# FPGA_IO.net
KiCad netlist of a schematic drawn in Altium Designer
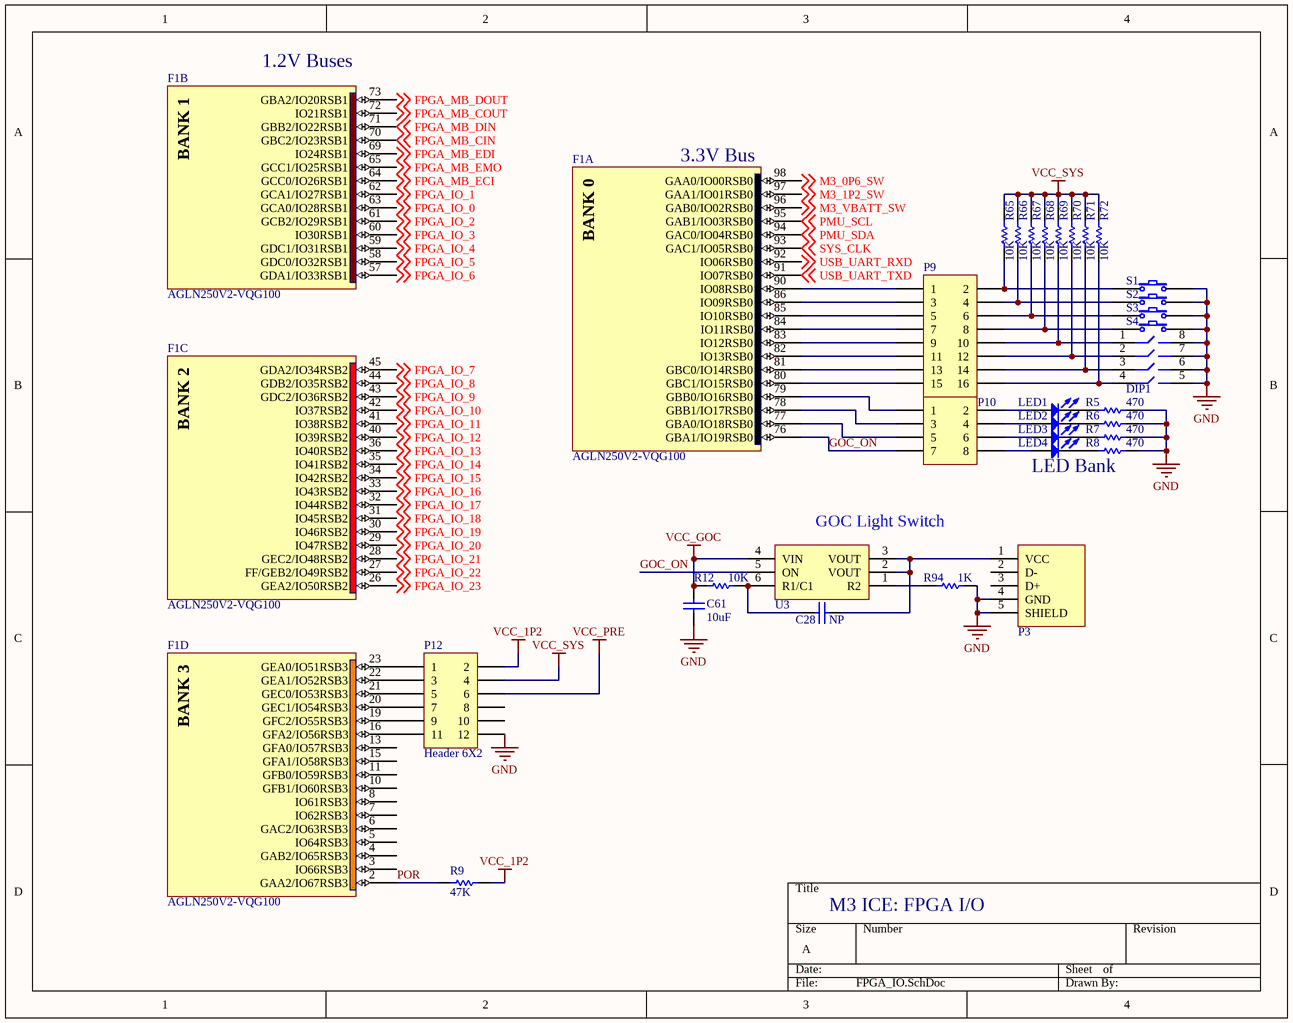
[diagram p0: FPGA_IO.SchDoc]

(export (version "E")
  (design (tool "Eeschema 10.0.6"))
  (components
    (comp (ref "C28")
      (value "NP")
      (footprint "0402")
      (description "Capacitor (Semiconductor SIM Model)")
      (fields (field (name "Comment") "Cap Semi") (field (name "PUBLISHER") "Altium Limited"))
      (libsource (lib "Miscellaneous Devices") (part "Cap Semi"))
    )
    (comp (ref "C61")
      (value "10uF")
      (footprint "0805")
      (description "Capacitor (Semiconductor SIM Model)")
      (fields
        (field (name "DISTPARTNO") "445-6857-1-ND")
        (field (name "MANPARTNO") "C2012X7R1A106K")
        (field (name "PUBLISHER") "Altium Limited")
      )
      (libsource (lib "M3") (part "Cap Chip"))
    )
    (comp (ref "DIP1")
      (value "ADE0404")
      (footprint "DIP-8")
      (description "4-DIP Switch")
      (fields (field (name "DISTPARTNO") "450-1364-ND"))
      (libsource (lib "M3") (part "ADE0404"))
    )
    (comp (ref "F1")
      (value "AGLN250V2-VQG100")
      (footprint "VQ100_N")
      (fields (field (name "DISTPARTNO") "1100-1134-ND") (field (name "PUBLISHER") "Altium Limited"))
      (libsource (lib "Actel IGLOO nano") (part "AGLN250V2-VQG100"))
    )
    (comp (ref "LED1")
      (value "LED 1206")
      (footprint "1206_LED")
      (fields (field (name "DISTPARTNO") "160-1169-1-ND") (field (name "MANPARTNO") "LTST-C150GKT"))
      (libsource (lib "M3") (part "LED 1206"))
    )
    (comp (ref "LED2")
      (value "LED 1206")
      (footprint "1206_LED")
      (fields (field (name "DISTPARTNO") "160-1169-1-ND") (field (name "MANPARTNO") "LTST-C150GKT"))
      (libsource (lib "M3") (part "LED 1206"))
    )
    (comp (ref "LED3")
      (value "LED 1206")
      (footprint "1206_LED")
      (fields (field (name "DISTPARTNO") "160-1169-1-ND") (field (name "MANPARTNO") "LTST-C150GKT"))
      (libsource (lib "M3") (part "LED 1206"))
    )
    (comp (ref "LED4")
      (value "LED 1206")
      (footprint "1206_LED")
      (fields (field (name "DISTPARTNO") "160-1169-1-ND") (field (name "MANPARTNO") "LTST-C150GKT"))
      (libsource (lib "M3") (part "LED 1206"))
    )
    (comp (ref "P3")
      (value "USB_HORIZONTAL")
      (footprint "USB_HORIZONTAL")
      (fields (field (name "DISTPARTNO") "A31726-ND") (field (name "MANPARTNO") "292303-1"))
      (libsource (lib "M3") (part "USB_HORIZONTAL"))
    )
    (comp (ref "P9")
      (value "Header 8X2")
      (footprint "HDR2X8")
      (description "Header, 8-Pin, Dual row")
      (fields (field (name "PUBLISHER") "Altium Limited"))
      (libsource (lib "Miscellaneous Connectors") (part "Header 8X2"))
    )
    (comp (ref "P10")
      (value "Header 4X2")
      (footprint "HDR2X4")
      (description "Header, 4-Pin, Dual row")
      (fields (field (name "PUBLISHER") "Altium Limited"))
      (libsource (lib "Miscellaneous Connectors") (part "Header 4X2"))
    )
    (comp (ref "P12")
      (value "Header 6X2")
      (footprint "HDR2X6")
      (description "Header, 6-Pin, Dual row")
      (fields (field (name "PUBLISHER") "Altium Limited"))
      (libsource (lib "Miscellaneous Connectors") (part "Header 6X2"))
    )
    (comp (ref "R5")
      (value "470")
      (footprint "0603")
      (description "Semiconductor Resistor")
      (fields
        (field (name "DISTPARTNO") "P470GCT-ND")
        (field (name "MANPARTNO") "ERJ-3GEYJ471V")
        (field (name "PUBLISHER") "Altium Limited")
      )
      (libsource (lib "M3") (part "Res Chip"))
    )
    (comp (ref "R6")
      (value "470")
      (footprint "0603")
      (description "Semiconductor Resistor")
      (fields
        (field (name "DISTPARTNO") "P470GCT-ND")
        (field (name "MANPARTNO") "ERJ-3GEYJ471V")
        (field (name "PUBLISHER") "Altium Limited")
      )
      (libsource (lib "M3") (part "Res Chip"))
    )
    (comp (ref "R7")
      (value "470")
      (footprint "0603")
      (description "Semiconductor Resistor")
      (fields
        (field (name "DISTPARTNO") "P470GCT-ND")
        (field (name "MANPARTNO") "ERJ-3GEYJ471V")
        (field (name "PUBLISHER") "Altium Limited")
      )
      (libsource (lib "M3") (part "Res Chip"))
    )
    (comp (ref "R8")
      (value "470")
      (footprint "0603")
      (description "Semiconductor Resistor")
      (fields
        (field (name "DISTPARTNO") "P470GCT-ND")
        (field (name "MANPARTNO") "ERJ-3GEYJ471V")
        (field (name "PUBLISHER") "Altium Limited")
      )
      (libsource (lib "M3") (part "Res Chip"))
    )
    (comp (ref "R9")
      (value "47K")
      (footprint "0603")
      (description "Semiconductor Resistor")
      (fields
        (field (name "DISTPARTNO") "P47KGCT-ND")
        (field (name "MANPARTNO") "ERJ-3GEYJ103V")
        (field (name "PUBLISHER") "Altium Limited")
      )
      (libsource (lib "M3") (part "Res Chip"))
    )
    (comp (ref "R12")
      (value "10K")
      (footprint "0402")
      (description "Semiconductor Resistor")
      (fields
        (field (name "MANPARTNO") "ERJ-2RKF1002X")
        (field (name "DISTPARTNO") "P10.0KLCT-ND")
        (field (name "PUBLISHER") "Altium Limited")
      )
      (libsource (lib "M3") (part "Res Chip"))
    )
    (comp (ref "R65")
      (value "10K")
      (footprint "0603")
      (description "Semiconductor Resistor")
      (fields
        (field (name "DISTPARTNO") "P10KGCT-ND")
        (field (name "MANPARTNO") "ERJ-3GEYJ103V")
        (field (name "PUBLISHER") "Altium Limited")
      )
      (libsource (lib "M3") (part "Res Chip"))
    )
    (comp (ref "R66")
      (value "10K")
      (footprint "0603")
      (description "Semiconductor Resistor")
      (fields
        (field (name "DISTPARTNO") "P10KGCT-ND")
        (field (name "MANPARTNO") "ERJ-3GEYJ103V")
        (field (name "PUBLISHER") "Altium Limited")
      )
      (libsource (lib "M3") (part "Res Chip"))
    )
    (comp (ref "R67")
      (value "10K")
      (footprint "0603")
      (description "Semiconductor Resistor")
      (fields
        (field (name "DISTPARTNO") "P10KGCT-ND")
        (field (name "MANPARTNO") "ERJ-3GEYJ103V")
        (field (name "PUBLISHER") "Altium Limited")
      )
      (libsource (lib "M3") (part "Res Chip"))
    )
    (comp (ref "R68")
      (value "10K")
      (footprint "0603")
      (description "Semiconductor Resistor")
      (fields
        (field (name "DISTPARTNO") "P10KGCT-ND")
        (field (name "MANPARTNO") "ERJ-3GEYJ103V")
        (field (name "PUBLISHER") "Altium Limited")
      )
      (libsource (lib "M3") (part "Res Chip"))
    )
    (comp (ref "R69")
      (value "10K")
      (footprint "0603")
      (description "Semiconductor Resistor")
      (fields
        (field (name "DISTPARTNO") "P10KGCT-ND")
        (field (name "MANPARTNO") "ERJ-3GEYJ103V")
        (field (name "PUBLISHER") "Altium Limited")
      )
      (libsource (lib "M3") (part "Res Chip"))
    )
    (comp (ref "R70")
      (value "10K")
      (footprint "0603")
      (description "Semiconductor Resistor")
      (fields
        (field (name "DISTPARTNO") "P10KGCT-ND")
        (field (name "MANPARTNO") "ERJ-3GEYJ103V")
        (field (name "PUBLISHER") "Altium Limited")
      )
      (libsource (lib "M3") (part "Res Chip"))
    )
    (comp (ref "R71")
      (value "10K")
      (footprint "0603")
      (description "Semiconductor Resistor")
      (fields
        (field (name "DISTPARTNO") "P10KGCT-ND")
        (field (name "MANPARTNO") "ERJ-3GEYJ103V")
        (field (name "PUBLISHER") "Altium Limited")
      )
      (libsource (lib "M3") (part "Res Chip"))
    )
    (comp (ref "R72")
      (value "10K")
      (footprint "0603")
      (description "Semiconductor Resistor")
      (fields
        (field (name "DISTPARTNO") "P10KGCT-ND")
        (field (name "MANPARTNO") "ERJ-3GEYJ103V")
        (field (name "PUBLISHER") "Altium Limited")
      )
      (libsource (lib "M3") (part "Res Chip"))
    )
    (comp (ref "R94")
      (value "1K")
      (footprint "0402")
      (description "Semiconductor Resistor")
      (fields
        (field (name "MANPARTNO") "ERJ-2RKF1001X")
        (field (name "DISTPARTNO") "P1.00KLCT-ND")
        (field (name "PUBLISHER") "Altium Limited")
      )
      (libsource (lib "M3") (part "Res Chip"))
    )
    (comp (ref "S1")
      (value "EVQ-PAE04M")
      (footprint "EVQPA")
      (description "Switch Push")
      (fields (field (name "DISTPARTNO") "P8008S-ND"))
      (libsource (lib "M3") (part "EVQ-PAE04M"))
    )
    (comp (ref "S2")
      (value "EVQ-PAE04M")
      (footprint "EVQPA")
      (description "Switch Push")
      (fields (field (name "DISTPARTNO") "P8008S-ND"))
      (libsource (lib "M3") (part "EVQ-PAE04M"))
    )
    (comp (ref "S3")
      (value "EVQ-PAE04M")
      (footprint "EVQPA")
      (description "Switch Push")
      (fields (field (name "DISTPARTNO") "P8008S-ND"))
      (libsource (lib "M3") (part "EVQ-PAE04M"))
    )
    (comp (ref "S4")
      (value "EVQ-PAE04M")
      (footprint "EVQPA")
      (description "Switch Push")
      (fields (field (name "DISTPARTNO") "P8008S-ND"))
      (libsource (lib "M3") (part "EVQ-PAE04M"))
    )
    (comp (ref "U3")
      (value "FDC6330L")
      (footprint "SUPERSOT-6")
      (description "HS Switch")
      (fields (field (name "DISTPARTNO") "FDC6330LCT-ND"))
      (libsource (lib "M3") (part "FDC6330L"))
    )
  )
  (nets
    (net (code "1") (name "/GOC_ON") (class "Default")
      (node (ref "F1") (pin "76") (pinfunction "GBA1/IO19RSB0_76") (pintype "bidirectional"))
      (node (ref "P10") (pin "7") (pinfunction "7_7") (pintype "passive"))
      (node (ref "U3") (pin "5") (pinfunction "ON_5") (pintype "passive"))
    )
    (net (code "2") (name "/POR") (class "Default")
      (node (ref "F1") (pin "2") (pinfunction "GAA2/IO67RSB3_2") (pintype "bidirectional"))
      (node (ref "R9") (pin "1") (pinfunction "1_1") (pintype "passive"))
    )
    (net (code "3") (name "FPGA_IO_0") (class "Default")
      (node (ref "F1") (pin "63") (pinfunction "GCA0/IO28RSB1_63") (pintype "bidirectional"))
    )
    (net (code "4") (name "FPGA_IO_1") (class "Default")
      (node (ref "F1") (pin "62") (pinfunction "GCA1/IO27RSB1_62") (pintype "bidirectional"))
    )
    (net (code "5") (name "FPGA_IO_2") (class "Default")
      (node (ref "F1") (pin "61") (pinfunction "GCB2/IO29RSB1_61") (pintype "bidirectional"))
    )
    (net (code "6") (name "FPGA_IO_3") (class "Default")
      (node (ref "F1") (pin "60") (pinfunction "IO30RSB1_60") (pintype "bidirectional"))
    )
    (net (code "7") (name "FPGA_IO_4") (class "Default")
      (node (ref "F1") (pin "59") (pinfunction "GDC1/IO31RSB1_59") (pintype "bidirectional"))
    )
    (net (code "8") (name "FPGA_IO_5") (class "Default")
      (node (ref "F1") (pin "58") (pinfunction "GDC0/IO32RSB1_58") (pintype "bidirectional"))
    )
    (net (code "9") (name "FPGA_IO_6") (class "Default")
      (node (ref "F1") (pin "57") (pinfunction "GDA1/IO33RSB1_57") (pintype "bidirectional"))
    )
    (net (code "10") (name "FPGA_IO_7") (class "Default")
      (node (ref "F1") (pin "45") (pinfunction "GDA2/IO34RSB2_45") (pintype "bidirectional"))
    )
    (net (code "11") (name "FPGA_IO_8") (class "Default")
      (node (ref "F1") (pin "44") (pinfunction "GDB2/IO35RSB2_44") (pintype "bidirectional"))
    )
    (net (code "12") (name "FPGA_IO_9") (class "Default")
      (node (ref "F1") (pin "43") (pinfunction "GDC2/IO36RSB2_43") (pintype "bidirectional"))
    )
    (net (code "13") (name "FPGA_IO_10") (class "Default")
      (node (ref "F1") (pin "42") (pinfunction "IO37RSB2_42") (pintype "bidirectional"))
    )
    (net (code "14") (name "FPGA_IO_11") (class "Default")
      (node (ref "F1") (pin "41") (pinfunction "IO38RSB2_41") (pintype "bidirectional"))
    )
    (net (code "15") (name "FPGA_IO_12") (class "Default")
      (node (ref "F1") (pin "40") (pinfunction "IO39RSB2_40") (pintype "bidirectional"))
    )
    (net (code "16") (name "FPGA_IO_13") (class "Default")
      (node (ref "F1") (pin "36") (pinfunction "IO40RSB2_36") (pintype "bidirectional"))
    )
    (net (code "17") (name "FPGA_IO_14") (class "Default")
      (node (ref "F1") (pin "35") (pinfunction "IO41RSB2_35") (pintype "bidirectional"))
    )
    (net (code "18") (name "FPGA_IO_15") (class "Default")
      (node (ref "F1") (pin "34") (pinfunction "IO42RSB2_34") (pintype "bidirectional"))
    )
    (net (code "19") (name "FPGA_IO_16") (class "Default")
      (node (ref "F1") (pin "33") (pinfunction "IO43RSB2_33") (pintype "bidirectional"))
    )
    (net (code "20") (name "FPGA_IO_17") (class "Default")
      (node (ref "F1") (pin "32") (pinfunction "IO44RSB2_32") (pintype "bidirectional"))
    )
    (net (code "21") (name "FPGA_IO_18") (class "Default")
      (node (ref "F1") (pin "31") (pinfunction "IO45RSB2_31") (pintype "bidirectional"))
    )
    (net (code "22") (name "FPGA_IO_19") (class "Default")
      (node (ref "F1") (pin "30") (pinfunction "IO46RSB2_30") (pintype "bidirectional"))
    )
    (net (code "23") (name "FPGA_IO_20") (class "Default")
      (node (ref "F1") (pin "29") (pinfunction "IO47RSB2_29") (pintype "bidirectional"))
    )
    (net (code "24") (name "FPGA_IO_21") (class "Default")
      (node (ref "F1") (pin "28") (pinfunction "GEC2/IO48RSB2_28") (pintype "bidirectional"))
    )
    (net (code "25") (name "FPGA_IO_22") (class "Default")
      (node (ref "F1") (pin "27") (pinfunction "FF/GEB2/IO49RSB2_27") (pintype "bidirectional"))
    )
    (net (code "26") (name "FPGA_IO_23") (class "Default")
      (node (ref "F1") (pin "26") (pinfunction "GEA2/IO50RSB2_26") (pintype "bidirectional"))
    )
    (net (code "27") (name "FPGA_MB_CIN") (class "Default")
      (node (ref "F1") (pin "70") (pinfunction "GBC2/IO23RSB1_70") (pintype "bidirectional"))
    )
    (net (code "28") (name "FPGA_MB_COUT") (class "Default")
      (node (ref "F1") (pin "72") (pinfunction "IO21RSB1_72") (pintype "bidirectional"))
    )
    (net (code "29") (name "FPGA_MB_DIN") (class "Default")
      (node (ref "F1") (pin "71") (pinfunction "GBB2/IO22RSB1_71") (pintype "bidirectional"))
    )
    (net (code "30") (name "FPGA_MB_DOUT") (class "Default")
      (node (ref "F1") (pin "73") (pinfunction "GBA2/IO20RSB1_73") (pintype "bidirectional"))
    )
    (net (code "31") (name "FPGA_MB_ECI") (class "Default")
      (node (ref "F1") (pin "64") (pinfunction "GCC0/IO26RSB1_64") (pintype "bidirectional"))
    )
    (net (code "32") (name "FPGA_MB_EDI") (class "Default")
      (node (ref "F1") (pin "69") (pinfunction "IO24RSB1_69") (pintype "bidirectional"))
    )
    (net (code "33") (name "FPGA_MB_EMO") (class "Default")
      (node (ref "F1") (pin "65") (pinfunction "GCC1/IO25RSB1_65") (pintype "bidirectional"))
    )
    (net (code "34") (name "GND") (class "Default")
      (node (ref "C61") (pin "2") (pinfunction "2_2") (pintype "passive"))
      (node (ref "DIP1") (pin "5") (pinfunction "5_5") (pintype "passive"))
      (node (ref "DIP1") (pin "6") (pinfunction "6_6") (pintype "passive"))
      (node (ref "DIP1") (pin "7") (pinfunction "7_7") (pintype "passive"))
      (node (ref "DIP1") (pin "8") (pinfunction "8_8") (pintype "passive"))
      (node (ref "P12") (pin "12") (pinfunction "12_12") (pintype "passive"))
      (node (ref "P3") (pin "4") (pinfunction "GND_4") (pintype "passive"))
      (node (ref "P3") (pin "5") (pinfunction "SHIELD_5") (pintype "passive"))
      (node (ref "R5") (pin "1") (pinfunction "1_1") (pintype "passive"))
      (node (ref "R6") (pin "1") (pinfunction "1_1") (pintype "passive"))
      (node (ref "R7") (pin "1") (pinfunction "1_1") (pintype "passive"))
      (node (ref "R8") (pin "1") (pinfunction "1_1") (pintype "passive"))
      (node (ref "R94") (pin "2") (pinfunction "2_2") (pintype "passive"))
      (node (ref "S1") (pin "2") (pinfunction "2_2") (pintype "passive"))
      (node (ref "S2") (pin "2") (pinfunction "2_2") (pintype "passive"))
      (node (ref "S3") (pin "2") (pinfunction "2_2") (pintype "passive"))
      (node (ref "S4") (pin "2") (pinfunction "2_2") (pintype "passive"))
    )
    (net (code "35") (name "M3_0P6_SW") (class "Default")
      (node (ref "F1") (pin "98") (pinfunction "GAA0/IO00RSB0_98") (pintype "bidirectional"))
    )
    (net (code "36") (name "M3_1P2_SW") (class "Default")
      (node (ref "F1") (pin "97") (pinfunction "GAA1/IO01RSB0_97") (pintype "bidirectional"))
    )
    (net (code "37") (name "M3_VBATT_SW") (class "Default")
      (node (ref "F1") (pin "96") (pinfunction "GAB0/IO02RSB0_96") (pintype "bidirectional"))
    )
    (net (code "38") (name "Net-(DIP1-Pad1)") (class "Default")
      (node (ref "DIP1") (pin "1") (pinfunction "1_1") (pintype "passive"))
      (node (ref "P9") (pin "10") (pinfunction "10_10") (pintype "passive"))
      (node (ref "R69") (pin "2") (pinfunction "2_2") (pintype "passive"))
    )
    (net (code "39") (name "Net-(DIP1-Pad2)") (class "Default")
      (node (ref "DIP1") (pin "2") (pinfunction "2_2") (pintype "passive"))
      (node (ref "P9") (pin "12") (pinfunction "12_12") (pintype "passive"))
      (node (ref "R70") (pin "2") (pinfunction "2_2") (pintype "passive"))
    )
    (net (code "40") (name "Net-(DIP1-Pad3)") (class "Default")
      (node (ref "DIP1") (pin "3") (pinfunction "3_3") (pintype "passive"))
      (node (ref "P9") (pin "14") (pinfunction "14_14") (pintype "passive"))
      (node (ref "R71") (pin "2") (pinfunction "2_2") (pintype "passive"))
    )
    (net (code "41") (name "Net-(DIP1-Pad4)") (class "Default")
      (node (ref "DIP1") (pin "4") (pinfunction "4_4") (pintype "passive"))
      (node (ref "P9") (pin "16") (pinfunction "16_16") (pintype "passive"))
      (node (ref "R72") (pin "2") (pinfunction "2_2") (pintype "passive"))
    )
    (net (code "42") (name "Net-(F1A-GBA0{slash}IO18RSB0)") (class "Default")
      (node (ref "F1") (pin "77") (pinfunction "GBA0/IO18RSB0_77") (pintype "bidirectional"))
      (node (ref "P10") (pin "5") (pinfunction "5_5") (pintype "passive"))
    )
    (net (code "43") (name "Net-(F1A-GBB0{slash}IO16RSB0)") (class "Default")
      (node (ref "F1") (pin "79") (pinfunction "GBB0/IO16RSB0_79") (pintype "bidirectional"))
      (node (ref "P10") (pin "1") (pinfunction "1_1") (pintype "passive"))
    )
    (net (code "44") (name "Net-(F1A-GBB1{slash}IO17RSB0)") (class "Default")
      (node (ref "F1") (pin "78") (pinfunction "GBB1/IO17RSB0_78") (pintype "bidirectional"))
      (node (ref "P10") (pin "3") (pinfunction "3_3") (pintype "passive"))
    )
    (net (code "45") (name "Net-(F1A-GBC0{slash}IO14RSB0)") (class "Default")
      (node (ref "F1") (pin "81") (pinfunction "GBC0/IO14RSB0_81") (pintype "bidirectional"))
      (node (ref "P9") (pin "13") (pinfunction "13_13") (pintype "passive"))
    )
    (net (code "46") (name "Net-(F1A-GBC1{slash}IO15RSB0)") (class "Default")
      (node (ref "F1") (pin "80") (pinfunction "GBC1/IO15RSB0_80") (pintype "bidirectional"))
      (node (ref "P9") (pin "15") (pinfunction "15_15") (pintype "passive"))
    )
    (net (code "47") (name "Net-(F1A-IO08RSB0)") (class "Default")
      (node (ref "F1") (pin "90") (pinfunction "IO08RSB0_90") (pintype "bidirectional"))
      (node (ref "P9") (pin "1") (pinfunction "1_1") (pintype "passive"))
    )
    (net (code "48") (name "Net-(F1A-IO09RSB0)") (class "Default")
      (node (ref "F1") (pin "86") (pinfunction "IO09RSB0_86") (pintype "bidirectional"))
      (node (ref "P9") (pin "3") (pinfunction "3_3") (pintype "passive"))
    )
    (net (code "49") (name "Net-(F1A-IO10RSB0)") (class "Default")
      (node (ref "F1") (pin "85") (pinfunction "IO10RSB0_85") (pintype "bidirectional"))
      (node (ref "P9") (pin "5") (pinfunction "5_5") (pintype "passive"))
    )
    (net (code "50") (name "Net-(F1A-IO11RSB0)") (class "Default")
      (node (ref "F1") (pin "84") (pinfunction "IO11RSB0_84") (pintype "bidirectional"))
      (node (ref "P9") (pin "7") (pinfunction "7_7") (pintype "passive"))
    )
    (net (code "51") (name "Net-(F1A-IO12RSB0)") (class "Default")
      (node (ref "F1") (pin "83") (pinfunction "IO12RSB0_83") (pintype "bidirectional"))
      (node (ref "P9") (pin "9") (pinfunction "9_9") (pintype "passive"))
    )
    (net (code "52") (name "Net-(F1A-IO13RSB0)") (class "Default")
      (node (ref "F1") (pin "82") (pinfunction "IO13RSB0_82") (pintype "bidirectional"))
      (node (ref "P9") (pin "11") (pinfunction "11_11") (pintype "passive"))
    )
    (net (code "53") (name "Net-(F1D-GEA0{slash}IO51RSB3)") (class "Default")
      (node (ref "F1") (pin "23") (pinfunction "GEA0/IO51RSB3_23") (pintype "bidirectional"))
      (node (ref "P12") (pin "1") (pinfunction "1_1") (pintype "passive"))
    )
    (net (code "54") (name "Net-(F1D-GEA1{slash}IO52RSB3)") (class "Default")
      (node (ref "F1") (pin "22") (pinfunction "GEA1/IO52RSB3_22") (pintype "bidirectional"))
      (node (ref "P12") (pin "3") (pinfunction "3_3") (pintype "passive"))
    )
    (net (code "55") (name "Net-(F1D-GEC0{slash}IO53RSB3)") (class "Default")
      (node (ref "F1") (pin "21") (pinfunction "GEC0/IO53RSB3_21") (pintype "bidirectional"))
      (node (ref "P12") (pin "5") (pinfunction "5_5") (pintype "passive"))
    )
    (net (code "56") (name "Net-(F1D-GEC1{slash}IO54RSB3)") (class "Default")
      (node (ref "F1") (pin "20") (pinfunction "GEC1/IO54RSB3_20") (pintype "bidirectional"))
      (node (ref "P12") (pin "7") (pinfunction "7_7") (pintype "passive"))
    )
    (net (code "57") (name "Net-(F1D-GFA2{slash}IO56RSB3)") (class "Default")
      (node (ref "F1") (pin "16") (pinfunction "GFA2/IO56RSB3_16") (pintype "bidirectional"))
      (node (ref "P12") (pin "11") (pinfunction "11_11") (pintype "passive"))
    )
    (net (code "58") (name "Net-(F1D-GFC2{slash}IO55RSB3)") (class "Default")
      (node (ref "F1") (pin "19") (pinfunction "GFC2/IO55RSB3_19") (pintype "bidirectional"))
      (node (ref "P12") (pin "9") (pinfunction "9_9") (pintype "passive"))
    )
    (net (code "59") (name "Net-(LED1-A)") (class "Default")
      (node (ref "LED1") (pin "1") (pinfunction "A_1") (pintype "passive"))
      (node (ref "P10") (pin "2") (pinfunction "2_2") (pintype "passive"))
    )
    (net (code "60") (name "Net-(LED1-K)") (class "Default")
      (node (ref "LED1") (pin "2") (pinfunction "K_2") (pintype "passive"))
      (node (ref "R5") (pin "2") (pinfunction "2_2") (pintype "passive"))
    )
    (net (code "61") (name "Net-(LED2-A)") (class "Default")
      (node (ref "LED2") (pin "1") (pinfunction "A_1") (pintype "passive"))
      (node (ref "P10") (pin "4") (pinfunction "4_4") (pintype "passive"))
    )
    (net (code "62") (name "Net-(LED2-K)") (class "Default")
      (node (ref "LED2") (pin "2") (pinfunction "K_2") (pintype "passive"))
      (node (ref "R6") (pin "2") (pinfunction "2_2") (pintype "passive"))
    )
    (net (code "63") (name "Net-(LED3-A)") (class "Default")
      (node (ref "LED3") (pin "1") (pinfunction "A_1") (pintype "passive"))
      (node (ref "P10") (pin "6") (pinfunction "6_6") (pintype "passive"))
    )
    (net (code "64") (name "Net-(LED3-K)") (class "Default")
      (node (ref "LED3") (pin "2") (pinfunction "K_2") (pintype "passive"))
      (node (ref "R7") (pin "2") (pinfunction "2_2") (pintype "passive"))
    )
    (net (code "65") (name "Net-(LED4-A)") (class "Default")
      (node (ref "LED4") (pin "1") (pinfunction "A_1") (pintype "passive"))
      (node (ref "P10") (pin "8") (pinfunction "8_8") (pintype "passive"))
    )
    (net (code "66") (name "Net-(LED4-K)") (class "Default")
      (node (ref "LED4") (pin "2") (pinfunction "K_2") (pintype "passive"))
      (node (ref "R8") (pin "2") (pinfunction "2_2") (pintype "passive"))
    )
    (net (code "67") (name "Net-(P3-VCC)") (class "Default")
      (node (ref "C28") (pin "1") (pinfunction "1_1") (pintype "passive"))
      (node (ref "P3") (pin "1") (pinfunction "VCC_1") (pintype "passive"))
      (node (ref "U3") (pin "2") (pinfunction "VOUT_2") (pintype "passive"))
      (node (ref "U3") (pin "3") (pinfunction "VOUT_3") (pintype "passive"))
    )
    (net (code "68") (name "Net-(P9-Pad2)") (class "Default")
      (node (ref "P9") (pin "2") (pinfunction "2_2") (pintype "passive"))
      (node (ref "R65") (pin "2") (pinfunction "2_2") (pintype "passive"))
      (node (ref "S1") (pin "1") (pinfunction "1_1") (pintype "passive"))
    )
    (net (code "69") (name "Net-(P9-Pad4)") (class "Default")
      (node (ref "P9") (pin "4") (pinfunction "4_4") (pintype "passive"))
      (node (ref "R66") (pin "2") (pinfunction "2_2") (pintype "passive"))
      (node (ref "S2") (pin "1") (pinfunction "1_1") (pintype "passive"))
    )
    (net (code "70") (name "Net-(P9-Pad6)") (class "Default")
      (node (ref "P9") (pin "6") (pinfunction "6_6") (pintype "passive"))
      (node (ref "R67") (pin "2") (pinfunction "2_2") (pintype "passive"))
      (node (ref "S3") (pin "1") (pinfunction "1_1") (pintype "passive"))
    )
    (net (code "71") (name "Net-(P9-Pad8)") (class "Default")
      (node (ref "P9") (pin "8") (pinfunction "8_8") (pintype "passive"))
      (node (ref "R68") (pin "2") (pinfunction "2_2") (pintype "passive"))
      (node (ref "S4") (pin "1") (pinfunction "1_1") (pintype "passive"))
    )
    (net (code "72") (name "Net-(U3-R1{slash}C1)") (class "Default")
      (node (ref "C28") (pin "2") (pinfunction "2_2") (pintype "passive"))
      (node (ref "R12") (pin "2") (pinfunction "2_2") (pintype "passive"))
      (node (ref "U3") (pin "6") (pinfunction "R1/C1_6") (pintype "passive"))
    )
    (net (code "73") (name "Net-(U3-R2)") (class "Default")
      (node (ref "R94") (pin "1") (pinfunction "1_1") (pintype "passive"))
      (node (ref "U3") (pin "1") (pinfunction "R2_1") (pintype "passive"))
    )
    (net (code "74") (name "PMU_SCL") (class "Default")
      (node (ref "F1") (pin "95") (pinfunction "GAB1/IO03RSB0_95") (pintype "bidirectional"))
    )
    (net (code "75") (name "PMU_SDA") (class "Default")
      (node (ref "F1") (pin "94") (pinfunction "GAC0/IO04RSB0_94") (pintype "bidirectional"))
    )
    (net (code "76") (name "SYS_CLK") (class "Default")
      (node (ref "F1") (pin "93") (pinfunction "GAC1/IO05RSB0_93") (pintype "bidirectional"))
    )
    (net (code "77") (name "USB_UART_RXD") (class "Default")
      (node (ref "F1") (pin "92") (pinfunction "IO06RSB0_92") (pintype "bidirectional"))
    )
    (net (code "78") (name "USB_UART_TXD") (class "Default")
      (node (ref "F1") (pin "91") (pinfunction "IO07RSB0_91") (pintype "bidirectional"))
    )
    (net (code "79") (name "VCC_1P2") (class "Default")
      (node (ref "P12") (pin "2") (pinfunction "2_2") (pintype "passive"))
      (node (ref "R9") (pin "2") (pinfunction "2_2") (pintype "passive"))
    )
    (net (code "80") (name "VCC_GOC") (class "Default")
      (node (ref "C61") (pin "1") (pinfunction "1_1") (pintype "passive"))
      (node (ref "R12") (pin "1") (pinfunction "1_1") (pintype "passive"))
      (node (ref "U3") (pin "4") (pinfunction "VIN_4") (pintype "passive"))
    )
    (net (code "81") (name "VCC_PRE") (class "Default")
      (node (ref "P12") (pin "6") (pinfunction "6_6") (pintype "passive"))
    )
    (net (code "82") (name "VCC_SYS") (class "Default")
      (node (ref "P12") (pin "4") (pinfunction "4_4") (pintype "passive"))
      (node (ref "R65") (pin "1") (pinfunction "1_1") (pintype "passive"))
      (node (ref "R66") (pin "1") (pinfunction "1_1") (pintype "passive"))
      (node (ref "R67") (pin "1") (pinfunction "1_1") (pintype "passive"))
      (node (ref "R68") (pin "1") (pinfunction "1_1") (pintype "passive"))
      (node (ref "R69") (pin "1") (pinfunction "1_1") (pintype "passive"))
      (node (ref "R70") (pin "1") (pinfunction "1_1") (pintype "passive"))
      (node (ref "R71") (pin "1") (pinfunction "1_1") (pintype "passive"))
      (node (ref "R72") (pin "1") (pinfunction "1_1") (pintype "passive"))
    )
    (net (code "83") (name "unconnected-(F1D-GAB2{slash}IO65RSB3-Pad4)") (class "Default")
      (node (ref "F1") (pin "4") (pinfunction "GAB2/IO65RSB3_4") (pintype "bidirectional"))
    )
    (net (code "84") (name "unconnected-(F1D-GAC2{slash}IO63RSB3-Pad6)") (class "Default")
      (node (ref "F1") (pin "6") (pinfunction "GAC2/IO63RSB3_6") (pintype "bidirectional"))
    )
    (net (code "85") (name "unconnected-(F1D-GFA0{slash}IO57RSB3-Pad13)") (class "Default")
      (node (ref "F1") (pin "13") (pinfunction "GFA0/IO57RSB3_13") (pintype "bidirectional"))
    )
    (net (code "86") (name "unconnected-(F1D-GFA1{slash}IO58RSB3-Pad15)") (class "Default")
      (node (ref "F1") (pin "15") (pinfunction "GFA1/IO58RSB3_15") (pintype "bidirectional"))
    )
    (net (code "87") (name "unconnected-(F1D-GFB0{slash}IO59RSB3-Pad11)") (class "Default")
      (node (ref "F1") (pin "11") (pinfunction "GFB0/IO59RSB3_11") (pintype "bidirectional"))
    )
    (net (code "88") (name "unconnected-(F1D-GFB1{slash}IO60RSB3-Pad10)") (class "Default")
      (node (ref "F1") (pin "10") (pinfunction "GFB1/IO60RSB3_10") (pintype "bidirectional"))
    )
    (net (code "89") (name "unconnected-(F1D-IO61RSB3-Pad8)") (class "Default")
      (node (ref "F1") (pin "8") (pinfunction "IO61RSB3_8") (pintype "bidirectional"))
    )
    (net (code "90") (name "unconnected-(F1D-IO62RSB3-Pad7)") (class "Default")
      (node (ref "F1") (pin "7") (pinfunction "IO62RSB3_7") (pintype "bidirectional"))
    )
    (net (code "91") (name "unconnected-(F1D-IO64RSB3-Pad5)") (class "Default")
      (node (ref "F1") (pin "5") (pinfunction "IO64RSB3_5") (pintype "bidirectional"))
    )
    (net (code "92") (name "unconnected-(F1D-IO66RSB3-Pad3)") (class "Default")
      (node (ref "F1") (pin "3") (pinfunction "IO66RSB3_3") (pintype "bidirectional"))
    )
    (net (code "93") (name "unconnected-(P3-D+-Pad3)") (class "Default")
      (node (ref "P3") (pin "3") (pinfunction "D+_3") (pintype "passive"))
    )
    (net (code "94") (name "unconnected-(P3-D--Pad2)") (class "Default")
      (node (ref "P3") (pin "2") (pinfunction "D-_2") (pintype "passive"))
    )
    (net (code "95") (name "unconnected-(P12-Pad8)") (class "Default")
      (node (ref "P12") (pin "8") (pinfunction "8_8") (pintype "passive"))
    )
    (net (code "96") (name "unconnected-(P12-Pad10)") (class "Default")
      (node (ref "P12") (pin "10") (pinfunction "10_10") (pintype "passive"))
    )
  )
)
